# tic_tac_toe.net
KiCad netlist of a schematic drawn in EAGLE
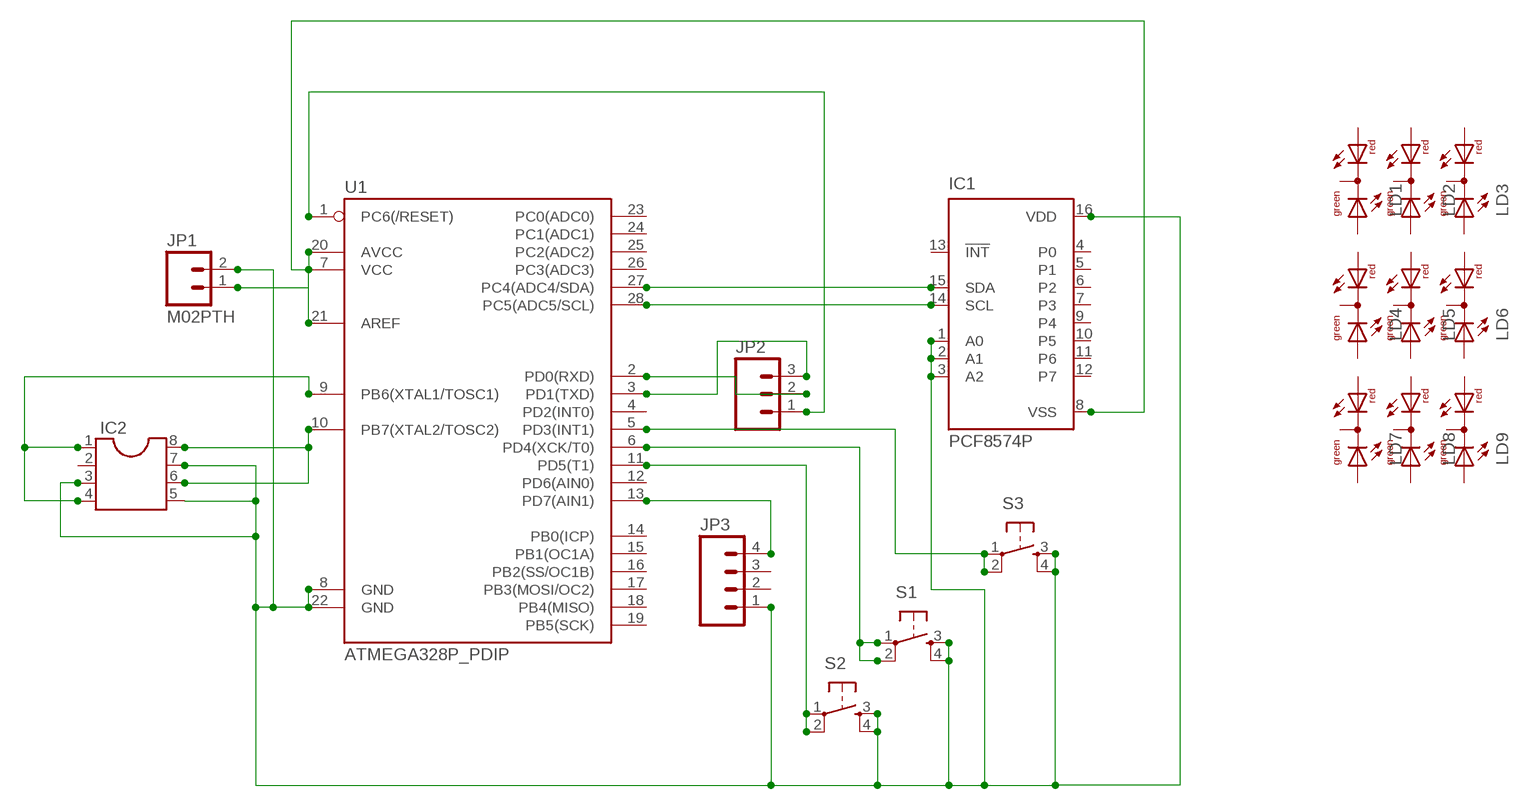
[diagram p0: schematic, sheet 1]

(export (version "E")
  (design (tool "Eeschema 10.0.6"))
  (components
    (comp (ref "IC1")
      (value "PCF8574P")
      (footprint "eagle-import:DIL16")
      (fields (field (name "MPN") "PCF8574PN"))
      (libsource (lib "eagle-import") (part "PCF8574P"))
    )
    (comp (ref "IC2")
      (value "DIL8S")
      (footprint "eagle-import:SOCKET-08")
      (libsource (lib "eagle-import") (part "DIL8S"))
    )
    (comp (ref "JP1")
      (value "M02PTH")
      (footprint "eagle-import:1X02")
      (libsource (lib "eagle-import") (part "M02PTH"))
    )
    (comp (ref "JP2")
      (value "M03PTH")
      (footprint "eagle-import:1X03")
      (libsource (lib "eagle-import") (part "M03PTH"))
    )
    (comp (ref "JP3")
      (value "M04PTH")
      (footprint "eagle-import:1X04")
      (libsource (lib "eagle-import") (part "M04PTH"))
    )
    (comp (ref "LD1")
      (value "DUOLED-RG-C")
      (footprint "eagle-import:DUOLED-C-5MM")
      (libsource (lib "eagle-import") (part "DUOLED-RG-C"))
    )
    (comp (ref "LD2")
      (value "DUOLED-RG-C")
      (footprint "eagle-import:DUOLED-C-5MM")
      (libsource (lib "eagle-import") (part "DUOLED-RG-C"))
    )
    (comp (ref "LD3")
      (value "DUOLED-RG-C")
      (footprint "eagle-import:DUOLED-C-5MM")
      (libsource (lib "eagle-import") (part "DUOLED-RG-C"))
    )
    (comp (ref "LD4")
      (value "DUOLED-RG-C")
      (footprint "eagle-import:DUOLED-C-5MM")
      (libsource (lib "eagle-import") (part "DUOLED-RG-C"))
    )
    (comp (ref "LD5")
      (value "DUOLED-RG-C")
      (footprint "eagle-import:DUOLED-C-5MM")
      (libsource (lib "eagle-import") (part "DUOLED-RG-C"))
    )
    (comp (ref "LD6")
      (value "DUOLED-RG-C")
      (footprint "eagle-import:DUOLED-C-5MM")
      (libsource (lib "eagle-import") (part "DUOLED-RG-C"))
    )
    (comp (ref "LD7")
      (value "DUOLED-RG-C")
      (footprint "eagle-import:DUOLED-C-5MM")
      (libsource (lib "eagle-import") (part "DUOLED-RG-C"))
    )
    (comp (ref "LD8")
      (value "DUOLED-RG-C")
      (footprint "eagle-import:DUOLED-C-5MM")
      (libsource (lib "eagle-import") (part "DUOLED-RG-C"))
    )
    (comp (ref "LD9")
      (value "DUOLED-RG-C")
      (footprint "eagle-import:DUOLED-C-5MM")
      (libsource (lib "eagle-import") (part "DUOLED-RG-C"))
    )
    (comp (ref "S1")
      (value "TAC_SWITCHPTH")
      (footprint "eagle-import:TACTILE-PTH")
      (libsource (lib "eagle-import") (part "TAC_SWITCHPTH"))
    )
    (comp (ref "S2")
      (value "TAC_SWITCHPTH")
      (footprint "eagle-import:TACTILE-PTH")
      (libsource (lib "eagle-import") (part "TAC_SWITCHPTH"))
    )
    (comp (ref "S3")
      (value "TAC_SWITCHPTH")
      (footprint "eagle-import:TACTILE-PTH")
      (libsource (lib "eagle-import") (part "TAC_SWITCHPTH"))
    )
    (comp (ref "U1")
      (value "ATMEGA328P_PDIP")
      (footprint "eagle-import:DIL28-3")
      (libsource (lib "eagle-import") (part "ATMEGA328P_PDIP"))
    )
  )
  (nets
    (net (code "1") (name "Net-(IC1-A0)") (class "Default")
      (node (ref "IC1") (pin "1") (pinfunction "A0_1") (pintype "input"))
      (node (ref "IC1") (pin "16") (pinfunction "VDD_16") (pintype "power_in"))
      (node (ref "IC1") (pin "2") (pinfunction "A1_2") (pintype "input"))
      (node (ref "IC1") (pin "3") (pinfunction "A2_3") (pintype "input"))
      (node (ref "IC2") (pin "3") (pinfunction "3_3") (pintype "passive"))
      (node (ref "IC2") (pin "5") (pinfunction "5_5") (pintype "passive"))
      (node (ref "IC2") (pin "7") (pinfunction "7_7") (pintype "passive"))
      (node (ref "JP1") (pin "2") (pinfunction "2_2") (pintype "passive"))
      (node (ref "JP3") (pin "1") (pinfunction "1_1") (pintype "passive"))
      (node (ref "S1") (pin "3") (pinfunction "3_3") (pintype "passive"))
      (node (ref "S1") (pin "4") (pinfunction "4_4") (pintype "passive"))
      (node (ref "S2") (pin "3") (pinfunction "3_3") (pintype "passive"))
      (node (ref "S2") (pin "4") (pinfunction "4_4") (pintype "passive"))
      (node (ref "S3") (pin "3") (pinfunction "3_3") (pintype "passive"))
      (node (ref "S3") (pin "4") (pinfunction "4_4") (pintype "passive"))
      (node (ref "U1") (pin "22") (pinfunction "GND_22") (pintype "bidirectional"))
      (node (ref "U1") (pin "8") (pinfunction "GND_8") (pintype "bidirectional"))
    )
    (net (code "2") (name "Net-(IC1-SCL)") (class "Default")
      (node (ref "IC1") (pin "14") (pinfunction "SCL_14") (pintype "input"))
      (node (ref "U1") (pin "28") (pinfunction "PC5(ADC5/SCL)_28") (pintype "bidirectional"))
    )
    (net (code "3") (name "Net-(IC1-SDA)") (class "Default")
      (node (ref "IC1") (pin "15") (pinfunction "SDA_15") (pintype "bidirectional"))
      (node (ref "U1") (pin "27") (pinfunction "PC4(ADC4/SDA)_27") (pintype "bidirectional"))
    )
    (net (code "4") (name "Net-(IC1-VSS)") (class "Default")
      (node (ref "IC1") (pin "8") (pinfunction "VSS_8") (pintype "power_in"))
      (node (ref "JP1") (pin "1") (pinfunction "1_1") (pintype "passive"))
      (node (ref "U1") (pin "20") (pinfunction "AVCC_20") (pintype "bidirectional"))
      (node (ref "U1") (pin "21") (pinfunction "AREF_21") (pintype "bidirectional"))
      (node (ref "U1") (pin "7") (pinfunction "VCC_7") (pintype "bidirectional"))
    )
    (net (code "5") (name "Net-(U1-PB6(XTAL1{slash}TOSC1))") (class "Default")
      (node (ref "IC2") (pin "1") (pinfunction "1_1") (pintype "passive"))
      (node (ref "IC2") (pin "4") (pinfunction "4_4") (pintype "passive"))
      (node (ref "U1") (pin "9") (pinfunction "PB6(XTAL1/TOSC1)_9") (pintype "bidirectional"))
    )
    (net (code "6") (name "Net-(U1-PB7(XTAL2{slash}TOSC2))") (class "Default")
      (node (ref "IC2") (pin "6") (pinfunction "6_6") (pintype "passive"))
      (node (ref "IC2") (pin "8") (pinfunction "8_8") (pintype "passive"))
      (node (ref "U1") (pin "10") (pinfunction "PB7(XTAL2/TOSC2)_10") (pintype "bidirectional"))
    )
    (net (code "7") (name "Net-(U1-PC6({slash}RESET))") (class "Default")
      (node (ref "JP2") (pin "1") (pinfunction "1_1") (pintype "passive"))
      (node (ref "U1") (pin "1") (pinfunction "PC6(/RESET)_1") (pintype "bidirectional"))
    )
    (net (code "8") (name "Net-(U1-PD0(RXD))") (class "Default")
      (node (ref "JP2") (pin "2") (pinfunction "2_2") (pintype "passive"))
      (node (ref "U1") (pin "2") (pinfunction "PD0(RXD)_2") (pintype "bidirectional"))
    )
    (net (code "9") (name "Net-(U1-PD1(TXD))") (class "Default")
      (node (ref "JP2") (pin "3") (pinfunction "3_3") (pintype "passive"))
      (node (ref "U1") (pin "3") (pinfunction "PD1(TXD)_3") (pintype "bidirectional"))
    )
    (net (code "10") (name "Net-(U1-PD3(INT1))") (class "Default")
      (node (ref "S3") (pin "1") (pinfunction "1_1") (pintype "passive"))
      (node (ref "S3") (pin "2") (pinfunction "2_2") (pintype "passive"))
      (node (ref "U1") (pin "5") (pinfunction "PD3(INT1)_5") (pintype "bidirectional"))
    )
    (net (code "11") (name "Net-(U1-PD4(XCK{slash}T0))") (class "Default")
      (node (ref "S1") (pin "1") (pinfunction "1_1") (pintype "passive"))
      (node (ref "S1") (pin "2") (pinfunction "2_2") (pintype "passive"))
      (node (ref "U1") (pin "6") (pinfunction "PD4(XCK/T0)_6") (pintype "bidirectional"))
    )
    (net (code "12") (name "Net-(U1-PD5(T1))") (class "Default")
      (node (ref "S2") (pin "1") (pinfunction "1_1") (pintype "passive"))
      (node (ref "S2") (pin "2") (pinfunction "2_2") (pintype "passive"))
      (node (ref "U1") (pin "11") (pinfunction "PD5(T1)_11") (pintype "bidirectional"))
    )
    (net (code "13") (name "Net-(U1-PD7(AIN1))") (class "Default")
      (node (ref "JP3") (pin "4") (pinfunction "4_4") (pintype "passive"))
      (node (ref "U1") (pin "13") (pinfunction "PD7(AIN1)_13") (pintype "bidirectional"))
    )
    (net (code "14") (name "unconnected-(IC1-P0-Pad4)") (class "Default")
      (node (ref "IC1") (pin "4") (pinfunction "P0_4") (pintype "bidirectional"))
    )
    (net (code "15") (name "unconnected-(IC1-P1-Pad5)") (class "Default")
      (node (ref "IC1") (pin "5") (pinfunction "P1_5") (pintype "bidirectional"))
    )
    (net (code "16") (name "unconnected-(IC1-P2-Pad6)") (class "Default")
      (node (ref "IC1") (pin "6") (pinfunction "P2_6") (pintype "bidirectional"))
    )
    (net (code "17") (name "unconnected-(IC1-P3-Pad7)") (class "Default")
      (node (ref "IC1") (pin "7") (pinfunction "P3_7") (pintype "bidirectional"))
    )
    (net (code "18") (name "unconnected-(IC1-P4-Pad9)") (class "Default")
      (node (ref "IC1") (pin "9") (pinfunction "P4_9") (pintype "bidirectional"))
    )
    (net (code "19") (name "unconnected-(IC1-P5-Pad10)") (class "Default")
      (node (ref "IC1") (pin "10") (pinfunction "P5_10") (pintype "bidirectional"))
    )
    (net (code "20") (name "unconnected-(IC1-P6-Pad11)") (class "Default")
      (node (ref "IC1") (pin "11") (pinfunction "P6_11") (pintype "bidirectional"))
    )
    (net (code "21") (name "unconnected-(IC1-P7-Pad12)") (class "Default")
      (node (ref "IC1") (pin "12") (pinfunction "P7_12") (pintype "bidirectional"))
    )
    (net (code "22") (name "unconnected-(IC1-~{INT}-Pad13)") (class "Default")
      (node (ref "IC1") (pin "13") (pinfunction "~{INT}_13") (pintype "output"))
    )
    (net (code "23") (name "unconnected-(IC2-Pad2)") (class "Default")
      (node (ref "IC2") (pin "2") (pinfunction "2_2") (pintype "passive"))
    )
    (net (code "24") (name "unconnected-(JP3-Pad2)") (class "Default")
      (node (ref "JP3") (pin "2") (pinfunction "2_2") (pintype "passive"))
    )
    (net (code "25") (name "unconnected-(JP3-Pad3)") (class "Default")
      (node (ref "JP3") (pin "3") (pinfunction "3_3") (pintype "passive"))
    )
    (net (code "26") (name "unconnected-(LD1-AG-PadAX)") (class "Default")
      (node (ref "LD1") (pin "AX") (pinfunction "AG_AX") (pintype "passive"))
    )
    (net (code "27") (name "unconnected-(LD1-PadAR)") (class "Default")
      (node (ref "LD1") (pin "AR") (pinfunction "AR_AR") (pintype "passive"))
    )
    (net (code "28") (name "unconnected-(LD1-PadC)") (class "Default")
      (node (ref "LD1") (pin "C") (pinfunction "C_C") (pintype "passive"))
    )
    (net (code "29") (name "unconnected-(LD2-AG-PadAX)") (class "Default")
      (node (ref "LD2") (pin "AX") (pinfunction "AG_AX") (pintype "passive"))
    )
    (net (code "30") (name "unconnected-(LD2-PadAR)") (class "Default")
      (node (ref "LD2") (pin "AR") (pinfunction "AR_AR") (pintype "passive"))
    )
    (net (code "31") (name "unconnected-(LD2-PadC)") (class "Default")
      (node (ref "LD2") (pin "C") (pinfunction "C_C") (pintype "passive"))
    )
    (net (code "32") (name "unconnected-(LD3-AG-PadAX)") (class "Default")
      (node (ref "LD3") (pin "AX") (pinfunction "AG_AX") (pintype "passive"))
    )
    (net (code "33") (name "unconnected-(LD3-PadAR)") (class "Default")
      (node (ref "LD3") (pin "AR") (pinfunction "AR_AR") (pintype "passive"))
    )
    (net (code "34") (name "unconnected-(LD3-PadC)") (class "Default")
      (node (ref "LD3") (pin "C") (pinfunction "C_C") (pintype "passive"))
    )
    (net (code "35") (name "unconnected-(LD4-AG-PadAX)") (class "Default")
      (node (ref "LD4") (pin "AX") (pinfunction "AG_AX") (pintype "passive"))
    )
    (net (code "36") (name "unconnected-(LD4-PadAR)") (class "Default")
      (node (ref "LD4") (pin "AR") (pinfunction "AR_AR") (pintype "passive"))
    )
    (net (code "37") (name "unconnected-(LD4-PadC)") (class "Default")
      (node (ref "LD4") (pin "C") (pinfunction "C_C") (pintype "passive"))
    )
    (net (code "38") (name "unconnected-(LD5-AG-PadAX)") (class "Default")
      (node (ref "LD5") (pin "AX") (pinfunction "AG_AX") (pintype "passive"))
    )
    (net (code "39") (name "unconnected-(LD5-PadAR)") (class "Default")
      (node (ref "LD5") (pin "AR") (pinfunction "AR_AR") (pintype "passive"))
    )
    (net (code "40") (name "unconnected-(LD5-PadC)") (class "Default")
      (node (ref "LD5") (pin "C") (pinfunction "C_C") (pintype "passive"))
    )
    (net (code "41") (name "unconnected-(LD6-AG-PadAX)") (class "Default")
      (node (ref "LD6") (pin "AX") (pinfunction "AG_AX") (pintype "passive"))
    )
    (net (code "42") (name "unconnected-(LD6-PadAR)") (class "Default")
      (node (ref "LD6") (pin "AR") (pinfunction "AR_AR") (pintype "passive"))
    )
    (net (code "43") (name "unconnected-(LD6-PadC)") (class "Default")
      (node (ref "LD6") (pin "C") (pinfunction "C_C") (pintype "passive"))
    )
    (net (code "44") (name "unconnected-(LD7-AG-PadAX)") (class "Default")
      (node (ref "LD7") (pin "AX") (pinfunction "AG_AX") (pintype "passive"))
    )
    (net (code "45") (name "unconnected-(LD7-PadAR)") (class "Default")
      (node (ref "LD7") (pin "AR") (pinfunction "AR_AR") (pintype "passive"))
    )
    (net (code "46") (name "unconnected-(LD7-PadC)") (class "Default")
      (node (ref "LD7") (pin "C") (pinfunction "C_C") (pintype "passive"))
    )
    (net (code "47") (name "unconnected-(LD8-AG-PadAX)") (class "Default")
      (node (ref "LD8") (pin "AX") (pinfunction "AG_AX") (pintype "passive"))
    )
    (net (code "48") (name "unconnected-(LD8-PadAR)") (class "Default")
      (node (ref "LD8") (pin "AR") (pinfunction "AR_AR") (pintype "passive"))
    )
    (net (code "49") (name "unconnected-(LD8-PadC)") (class "Default")
      (node (ref "LD8") (pin "C") (pinfunction "C_C") (pintype "passive"))
    )
    (net (code "50") (name "unconnected-(LD9-AG-PadAX)") (class "Default")
      (node (ref "LD9") (pin "AX") (pinfunction "AG_AX") (pintype "passive"))
    )
    (net (code "51") (name "unconnected-(LD9-PadAR)") (class "Default")
      (node (ref "LD9") (pin "AR") (pinfunction "AR_AR") (pintype "passive"))
    )
    (net (code "52") (name "unconnected-(LD9-PadC)") (class "Default")
      (node (ref "LD9") (pin "C") (pinfunction "C_C") (pintype "passive"))
    )
    (net (code "53") (name "unconnected-(U1-PB0(ICP)-Pad14)") (class "Default")
      (node (ref "U1") (pin "14") (pinfunction "PB0(ICP)_14") (pintype "bidirectional"))
    )
    (net (code "54") (name "unconnected-(U1-PB1(OC1A)-Pad15)") (class "Default")
      (node (ref "U1") (pin "15") (pinfunction "PB1(OC1A)_15") (pintype "bidirectional"))
    )
    (net (code "55") (name "unconnected-(U1-PB2(SS{slash}OC1B)-Pad16)") (class "Default")
      (node (ref "U1") (pin "16") (pinfunction "PB2(SS/OC1B)_16") (pintype "bidirectional"))
    )
    (net (code "56") (name "unconnected-(U1-PB3(MOSI{slash}OC2)-Pad17)") (class "Default")
      (node (ref "U1") (pin "17") (pinfunction "PB3(MOSI/OC2)_17") (pintype "bidirectional"))
    )
    (net (code "57") (name "unconnected-(U1-PB4(MISO)-Pad18)") (class "Default")
      (node (ref "U1") (pin "18") (pinfunction "PB4(MISO)_18") (pintype "bidirectional"))
    )
    (net (code "58") (name "unconnected-(U1-PB5(SCK)-Pad19)") (class "Default")
      (node (ref "U1") (pin "19") (pinfunction "PB5(SCK)_19") (pintype "bidirectional"))
    )
    (net (code "59") (name "unconnected-(U1-PC0(ADC0)-Pad23)") (class "Default")
      (node (ref "U1") (pin "23") (pinfunction "PC0(ADC0)_23") (pintype "bidirectional"))
    )
    (net (code "60") (name "unconnected-(U1-PC1(ADC1)-Pad24)") (class "Default")
      (node (ref "U1") (pin "24") (pinfunction "PC1(ADC1)_24") (pintype "bidirectional"))
    )
    (net (code "61") (name "unconnected-(U1-PC2(ADC2)-Pad25)") (class "Default")
      (node (ref "U1") (pin "25") (pinfunction "PC2(ADC2)_25") (pintype "bidirectional"))
    )
    (net (code "62") (name "unconnected-(U1-PC3(ADC3)-Pad26)") (class "Default")
      (node (ref "U1") (pin "26") (pinfunction "PC3(ADC3)_26") (pintype "bidirectional"))
    )
    (net (code "63") (name "unconnected-(U1-PD2(INT0)-Pad4)") (class "Default")
      (node (ref "U1") (pin "4") (pinfunction "PD2(INT0)_4") (pintype "bidirectional"))
    )
    (net (code "64") (name "unconnected-(U1-PD6(AIN0)-Pad12)") (class "Default")
      (node (ref "U1") (pin "12") (pinfunction "PD6(AIN0)_12") (pintype "bidirectional"))
    )
  )
)
